# nusense-mup-sensor.net
KiCad netlist of a schematic drawn in Altium Designer
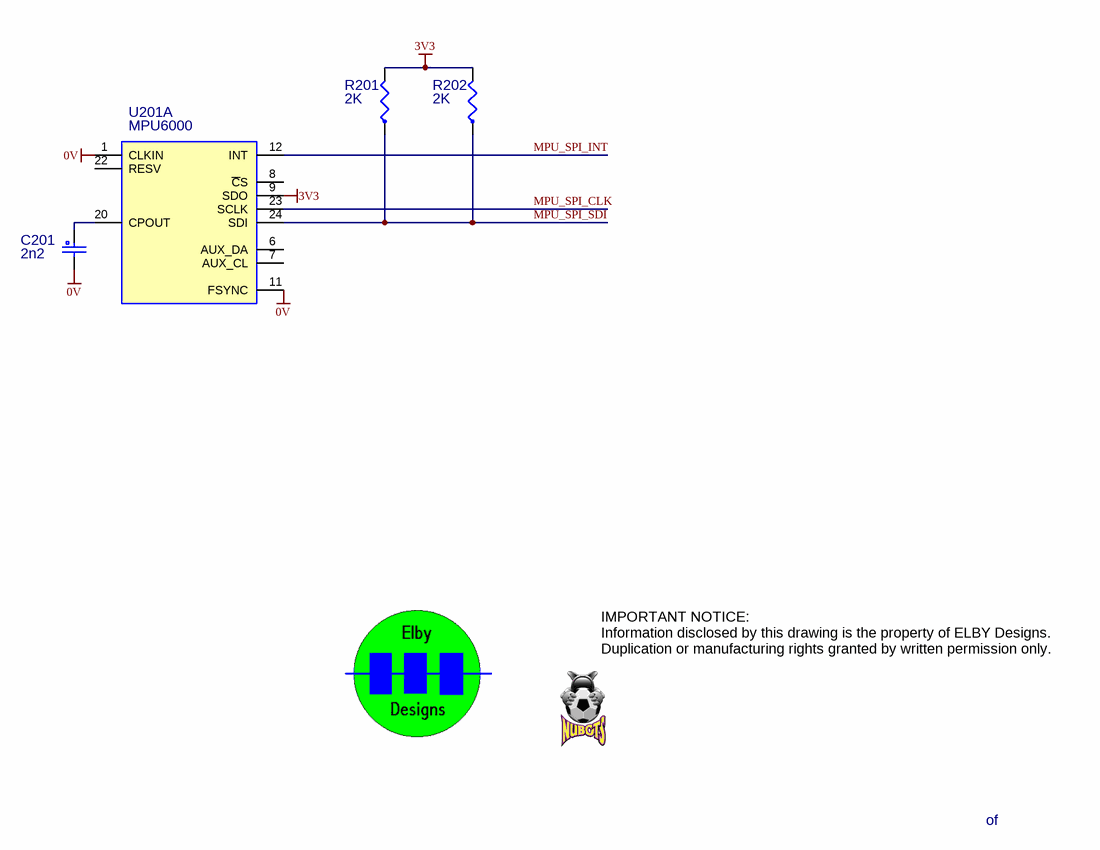
[diagram p0: nusense-mup-sensor.schdoc]

(export (version "E")
  (design (tool "Eeschema 10.0.6"))
  (components
    (comp (ref "C201")
      (value "2n2")
      (footprint "RAD-0.2(LB)")
      (description "63V 10% Metallised Polyester")
      (libsource (lib "capacitor") (part "CP-2N2F(LB)"))
    )
    (comp (ref "R201")
      (value "2K")
      (footprint "AXIAL-0.4(LB)")
      (description "0.5W 1% Metal Film Resistor")
      (libsource (lib "resistor") (part "RM-2K(LB)"))
    )
    (comp (ref "R202")
      (value "2K")
      (footprint "AXIAL-0.4(LB)")
      (description "0.5W 1% Metal Film Resistor")
      (libsource (lib "resistor") (part "RM-2K(LB)"))
    )
    (comp (ref "U201")
      (value "MPU6000")
      (description "Motion Tracking")
      (libsource (lib "NuBots") (part "MPU6000"))
    )
  )
  (nets
    (net (code "1") (name "/MPU_SPI_CLK") (class "Default")
      (node (ref "U201") (pin "23") (pinfunction "SCLK_23") (pintype "passive"))
    )
    (net (code "2") (name "/MPU_SPI_INT") (class "Default")
      (node (ref "U201") (pin "12") (pinfunction "INT_12") (pintype "passive"))
    )
    (net (code "3") (name "/MPU_SPI_SDI") (class "Default")
      (node (ref "R201") (pin "1") (pinfunction "1_1") (pintype "passive"))
      (node (ref "R202") (pin "1") (pinfunction "1_1") (pintype "passive"))
      (node (ref "U201") (pin "24") (pinfunction "SDI_24") (pintype "passive"))
    )
    (net (code "4") (name "0V") (class "Default")
      (node (ref "C201") (pin "2") (pintype "passive"))
      (node (ref "U201") (pin "1") (pinfunction "CLKIN_1") (pintype "passive"))
      (node (ref "U201") (pin "11") (pinfunction "FSYNC_11") (pintype "passive"))
    )
    (net (code "5") (name "3V3") (class "Default")
      (node (ref "R201") (pin "2") (pinfunction "2_2") (pintype "passive"))
      (node (ref "R202") (pin "2") (pinfunction "2_2") (pintype "passive"))
      (node (ref "U201") (pin "9") (pinfunction "SDO_9") (pintype "passive"))
    )
    (net (code "6") (name "Net-(U201A-CPOUT)") (class "Default")
      (node (ref "C201") (pin "1") (pintype "passive"))
      (node (ref "U201") (pin "20") (pinfunction "CPOUT_20") (pintype "passive"))
    )
    (net (code "7") (name "unconnected-(U201A-AUX_CL-Pad7)") (class "Default")
      (node (ref "U201") (pin "7") (pinfunction "AUX_CL_7") (pintype "passive"))
    )
    (net (code "8") (name "unconnected-(U201A-AUX_DA-Pad6)") (class "Default")
      (node (ref "U201") (pin "6") (pinfunction "AUX_DA_6") (pintype "passive"))
    )
    (net (code "9") (name "unconnected-(U201A-RESV-Pad22)") (class "Default")
      (node (ref "U201") (pin "22") (pinfunction "RESV_22") (pintype "passive"))
    )
    (net (code "10") (name "unconnected-(U201A-~{C}S-Pad8)") (class "Default")
      (node (ref "U201") (pin "8") (pinfunction "~{C}S_8") (pintype "passive"))
    )
  )
)
